# SMC_FrontPanel_ExtensionBoard_V14_5.net
KiCad netlist of a schematic drawn in EAGLE
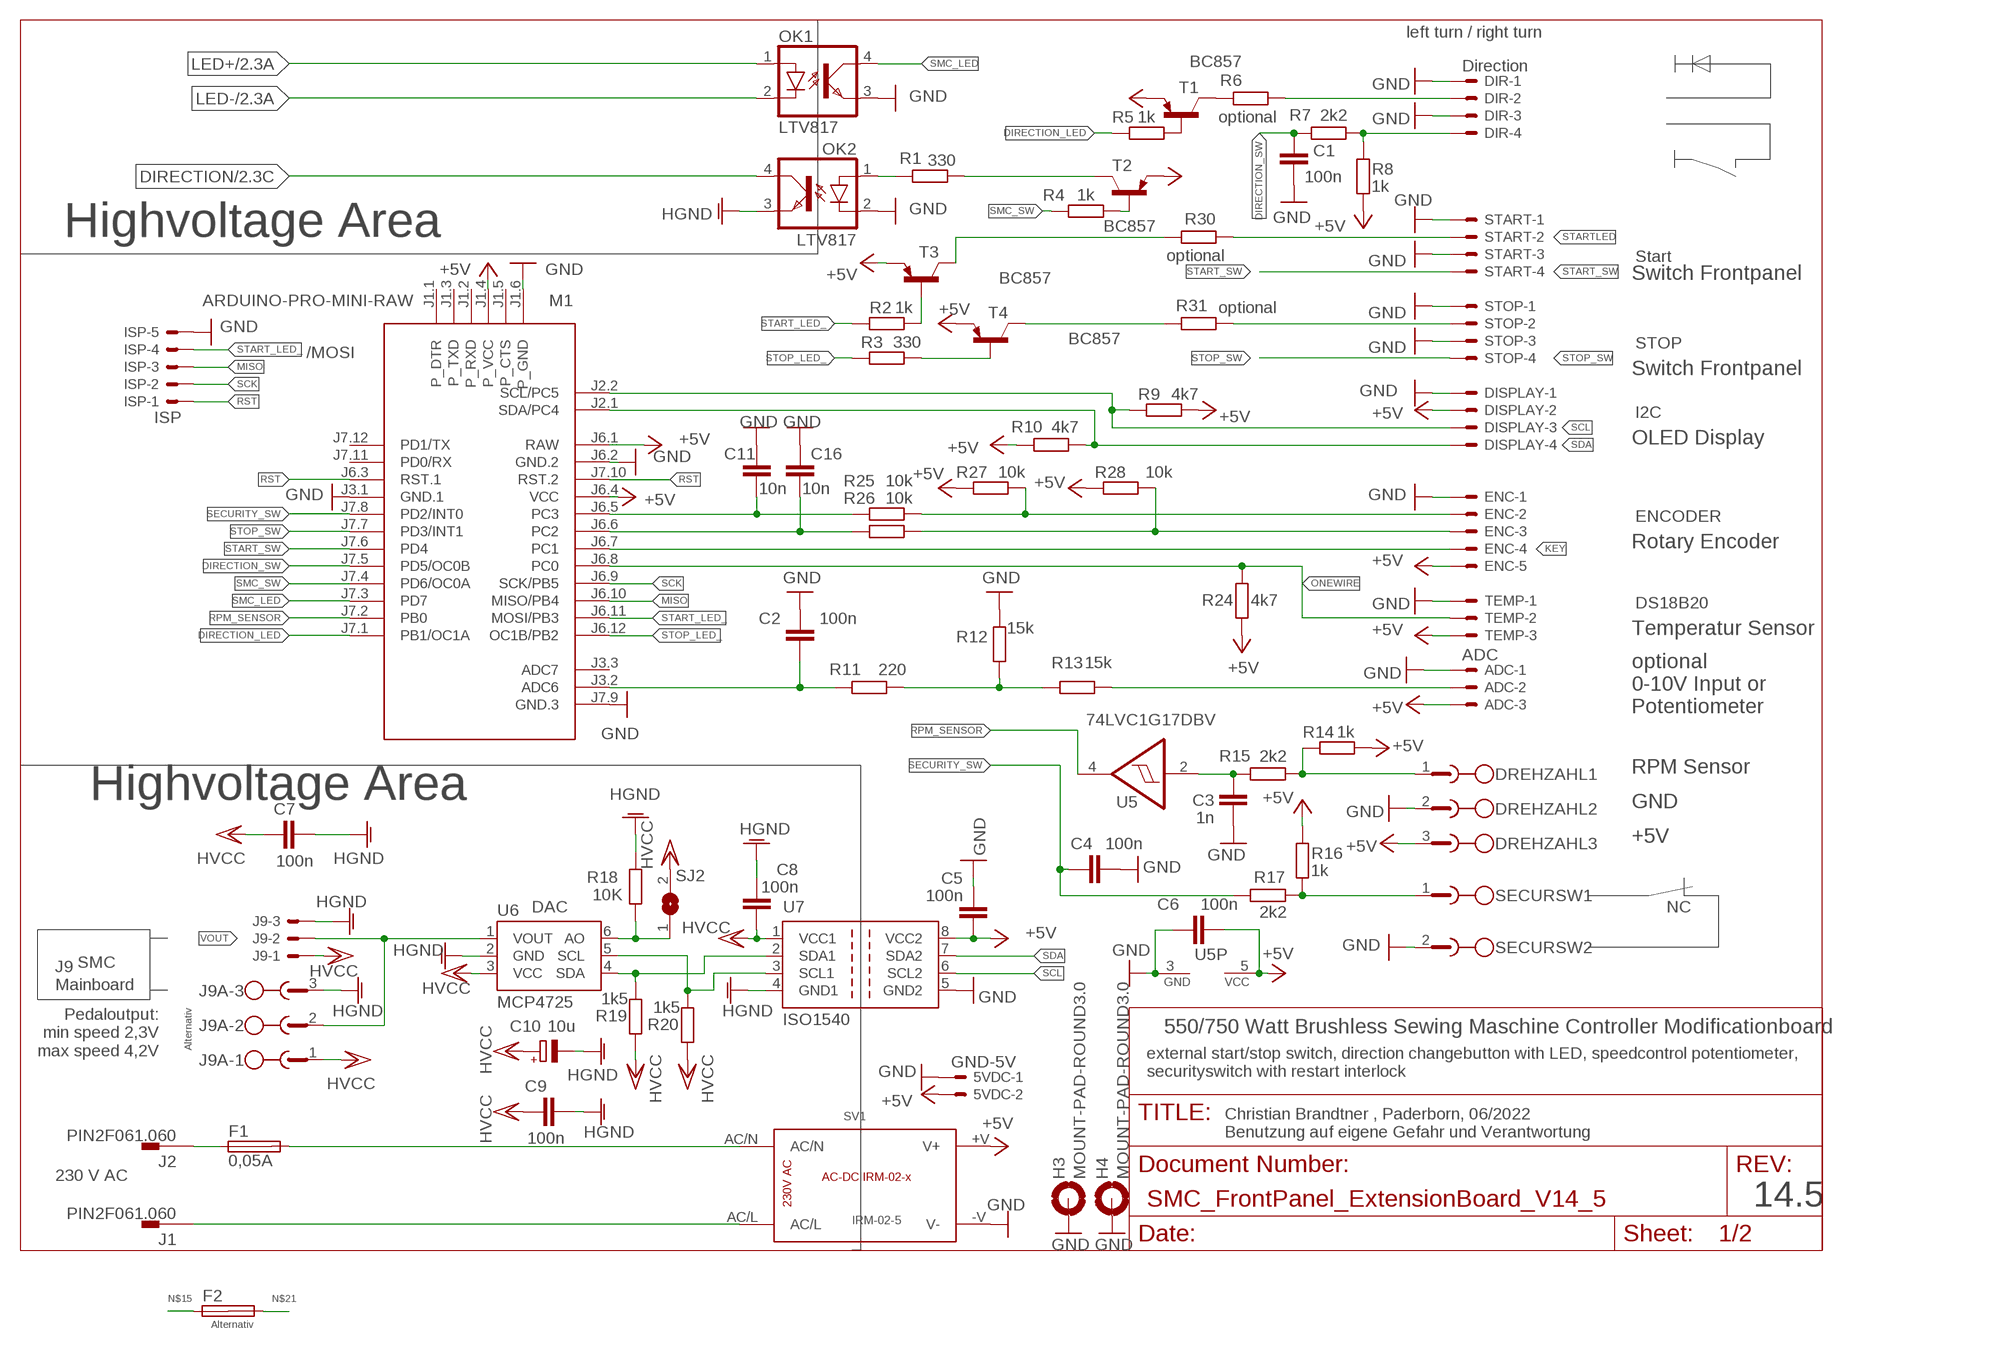
[diagram p0: schematic, sheet 1]
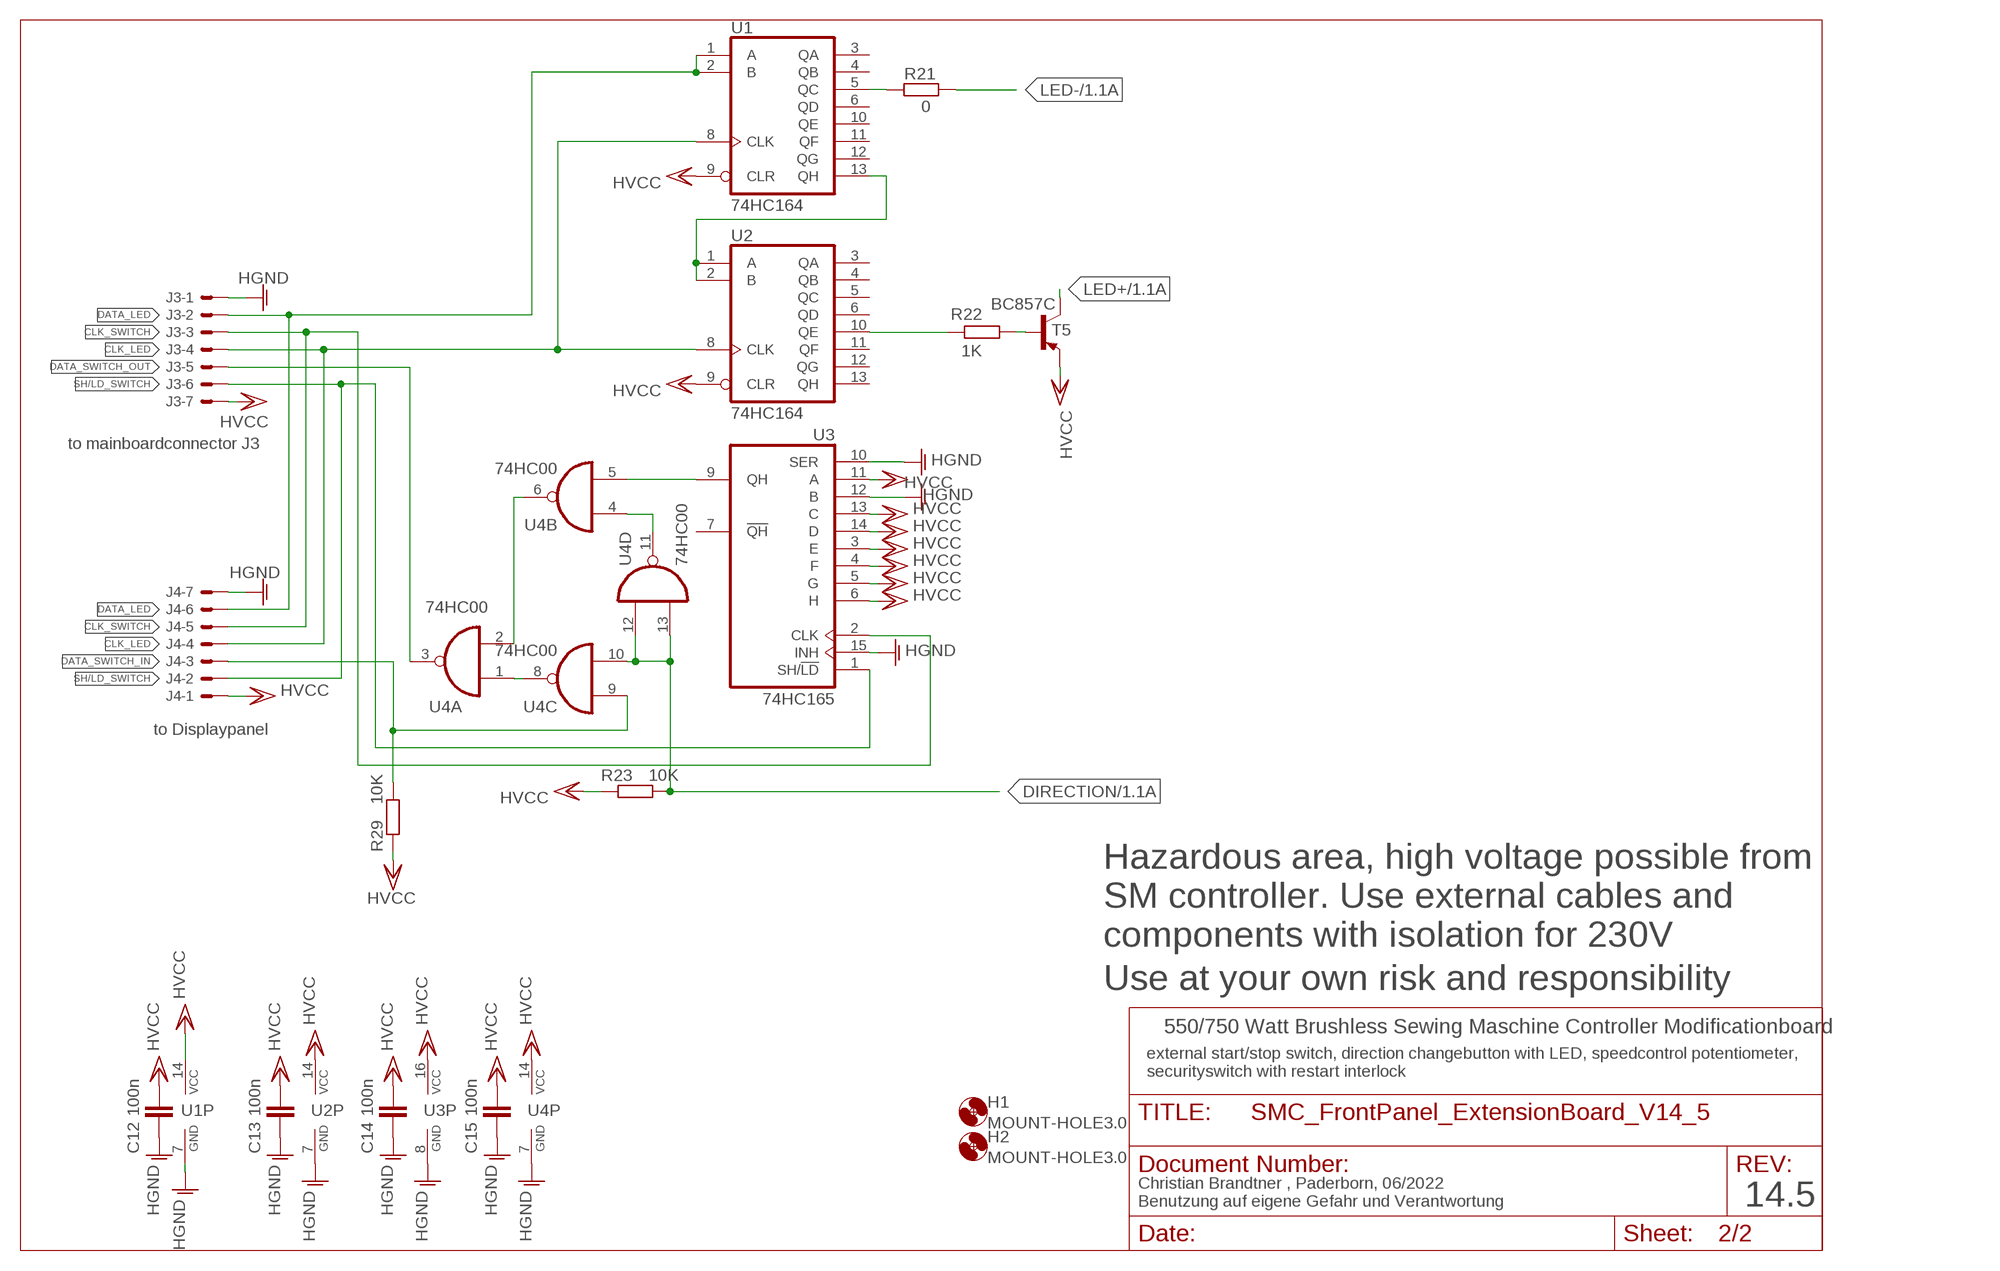
[diagram p1: schematic, sheet 2]

(export (version "E")
  (design (tool "Eeschema 10.0.6"))
  (components
    (comp (ref "C12")
      (value "100n")
      (footprint "eagle-import:C0805")
      (libsource (lib "eagle-import") (part "C-EUC0805"))
    )
    (comp (ref "C13")
      (value "100n")
      (footprint "eagle-import:C0805")
      (libsource (lib "eagle-import") (part "C-EUC0805"))
    )
    (comp (ref "C14")
      (value "100n")
      (footprint "eagle-import:C0805")
      (libsource (lib "eagle-import") (part "C-EUC0805"))
    )
    (comp (ref "C15")
      (value "100n")
      (footprint "eagle-import:C0805")
      (libsource (lib "eagle-import") (part "C-EUC0805"))
    )
    (comp (ref "H1")
      (value "MOUNT-HOLE3.0")
      (footprint "eagle-import:3,0")
      (libsource (lib "eagle-import") (part "MOUNT-HOLE3.0"))
    )
    (comp (ref "H2")
      (value "MOUNT-HOLE3.0")
      (footprint "eagle-import:3,0")
      (libsource (lib "eagle-import") (part "MOUNT-HOLE3.0"))
    )
    (comp (ref "J3")
      (value "to mainboardconnector J3")
      (footprint "eagle-import:JST-XH-07-PACKAGE-ROUND-PAD")
      (libsource (lib "eagle-import") (part "JST-XH-07-PIN-ROUND-PAD"))
    )
    (comp (ref "J4")
      (value "to Displaypanel")
      (footprint "eagle-import:JST-XH-07-PACKAGE-ROUND-PAD")
      (libsource (lib "eagle-import") (part "JST-XH-07-PIN-ROUND-PAD"))
    )
    (comp (ref "R21")
      (value "0")
      (footprint "eagle-import:R0805")
      (libsource (lib "eagle-import") (part "R-EU_R0805"))
    )
    (comp (ref "R22")
      (value "1K")
      (footprint "eagle-import:R0805")
      (libsource (lib "eagle-import") (part "R-EU_R0805"))
    )
    (comp (ref "R23")
      (value "10K")
      (footprint "eagle-import:R0805")
      (libsource (lib "eagle-import") (part "R-EU_R0805"))
    )
    (comp (ref "R29")
      (value "10K")
      (footprint "eagle-import:R0805")
      (libsource (lib "eagle-import") (part "R-EU_R0805"))
    )
    (comp (ref "T5")
      (value "BC857C")
      (footprint "eagle-import:SOT23-BEC")
      (libsource (lib "eagle-import") (part "-PNP-SOT23-BECBC857C"))
    )
    (comp (ref "U1")
      (value "74HC164")
      (footprint "eagle-import:SO14")
      (libsource (lib "eagle-import") (part "74164DHC"))
    )
    (comp (ref "U2")
      (value "74HC164")
      (footprint "eagle-import:SO14")
      (libsource (lib "eagle-import") (part "74164DHC"))
    )
    (comp (ref "U3")
      (value "74HC165")
      (footprint "eagle-import:SO16")
      (libsource (lib "eagle-import") (part "74165DHC"))
    )
    (comp (ref "U4")
      (value "74HC00")
      (footprint "eagle-import:SO14")
      (libsource (lib "eagle-import") (part "7400DHC"))
    )
    (comp (ref "5VDC")
      (value "GND-5V")
      (footprint "eagle-import:JST-XH-02-PACKAGE-ROUND-PAD")
      (libsource (lib "eagle-import") (part "JST-XH-02-PIN-ROUND-PAD"))
    )
    (comp (ref "ADC")
      (value "ADC")
      (footprint "eagle-import:JST-XH-03-PACKAGE-ROUND-PAD")
      (libsource (lib "eagle-import") (part "JST-XH-03-PIN-ROUND-PAD"))
    )
    (comp (ref "C1")
      (value "100n")
      (footprint "eagle-import:C0805")
      (libsource (lib "eagle-import") (part "C-EUC0805"))
    )
    (comp (ref "C2")
      (value "100n")
      (footprint "eagle-import:C0805")
      (libsource (lib "eagle-import") (part "C-EUC0805"))
    )
    (comp (ref "C3")
      (value "1n")
      (footprint "eagle-import:C0805")
      (libsource (lib "eagle-import") (part "C-EUC0805"))
    )
    (comp (ref "C4")
      (value "100n")
      (footprint "eagle-import:C0805")
      (libsource (lib "eagle-import") (part "C-EUC0805"))
    )
    (comp (ref "C5")
      (value "100n")
      (footprint "eagle-import:C0805")
      (libsource (lib "eagle-import") (part "C-EUC0805"))
    )
    (comp (ref "C6")
      (value "100n")
      (footprint "eagle-import:C0805")
      (libsource (lib "eagle-import") (part "C-EUC0805"))
    )
    (comp (ref "C7")
      (value "100n")
      (footprint "eagle-import:C0805")
      (libsource (lib "eagle-import") (part "C-EUC0805"))
    )
    (comp (ref "C8")
      (value "100n")
      (footprint "eagle-import:C0805")
      (libsource (lib "eagle-import") (part "C-EUC0805"))
    )
    (comp (ref "C9")
      (value "100n")
      (footprint "eagle-import:C0805")
      (libsource (lib "eagle-import") (part "C-EUC0805"))
    )
    (comp (ref "C10")
      (value "10u")
      (footprint "eagle-import:153CLV-0405")
      (libsource (lib "eagle-import") (part "CPOL-EU153CLV-0405"))
    )
    (comp (ref "C11")
      (value "10n")
      (footprint "eagle-import:C0805")
      (libsource (lib "eagle-import") (part "C-EUC0805"))
    )
    (comp (ref "C16")
      (value "10n")
      (footprint "eagle-import:C0805")
      (libsource (lib "eagle-import") (part "C-EUC0805"))
    )
    (comp (ref "DIR")
      (value "Direction")
      (footprint "eagle-import:JST-XH-04-PACKAGE-ROUND-PAD")
      (libsource (lib "eagle-import") (part "JST-XH-04-PIN-ROUND-PAD"))
    )
    (comp (ref "DISPLAY")
      (value "I2C")
      (footprint "eagle-import:JST-XH-04-PACKAGE-ROUND-PAD")
      (libsource (lib "eagle-import") (part "JST-XH-04-PIN-ROUND-PAD"))
    )
    (comp (ref "DREHZAHL")
      (value "MCV_1.5/3/-G-3.5")
      (footprint "eagle-import:1843619")
      (libsource (lib "eagle-import") (part "MCV_1.5/3/-G-3.5"))
    )
    (comp (ref "ENC")
      (value "ENCODER")
      (footprint "eagle-import:JST-XH-05-PACKAGE-ROUND-PAD")
      (libsource (lib "eagle-import") (part "JST-XH-05-PIN-ROUND-PAD"))
    )
    (comp (ref "F1")
      (value "0,05A")
      (footprint "eagle-import:MTA501100")
      (libsource (lib "eagle-import") (part "FUSE"))
    )
    (comp (ref "F2")
      (value "SHK20L")
      (footprint "eagle-import:SHK20L")
      (libsource (lib "eagle-import") (part "SHK20L"))
    )
    (comp (ref "H3")
      (value "MOUNT-PAD-ROUND3.0")
      (footprint "eagle-import:3,0-PAD")
      (libsource (lib "eagle-import") (part "MOUNT-PAD-ROUND3.0"))
    )
    (comp (ref "H4")
      (value "MOUNT-PAD-ROUND3.0")
      (footprint "eagle-import:3,0-PAD")
      (libsource (lib "eagle-import") (part "MOUNT-PAD-ROUND3.0"))
    )
    (comp (ref "ISP")
      (value "ISP")
      (footprint "eagle-import:JST-XH-05-PACKAGE-ROUND-PAD")
      (libsource (lib "eagle-import") (part "JST-XH-05-PIN-ROUND-PAD"))
    )
    (comp (ref "J1")
      (value "PIN2F061.060")
      (footprint "eagle-import:F061.060")
      (libsource (lib "eagle-import") (part "PIN2F061.060"))
    )
    (comp (ref "J2")
      (value "PIN2F061.060")
      (footprint "eagle-import:F061.060")
      (libsource (lib "eagle-import") (part "PIN2F061.060"))
    )
    (comp (ref "J9")
      (value "JST-XH-03-PIN-ROUND-PAD")
      (footprint "eagle-import:JST-XH-03-PACKAGE-ROUND-PAD")
      (libsource (lib "eagle-import") (part "JST-XH-03-PIN-ROUND-PAD"))
    )
    (comp (ref "J9A-")
      (value "MCV_1.5/3/-G-3.5")
      (footprint "eagle-import:1843619")
      (libsource (lib "eagle-import") (part "MCV_1.5/3/-G-3.5"))
    )
    (comp (ref "M1")
      (value "ARDUINO-PRO-MINI-RAW")
      (footprint "eagle-import:ARDUINO-PRO-MINI")
      (libsource (lib "eagle-import") (part "ARDUINO-PRO-MINI-RAW"))
    )
    (comp (ref "OK1")
      (value "LTV817")
      (footprint "eagle-import:SMD4-7")
      (fields (field (name "MF") "VISHAY/TELEFUNKEN") (field (name "MPN") "SFH6186-2"))
      (libsource (lib "eagle-import") (part "SFH618?6-2"))
    )
    (comp (ref "OK2")
      (value "LTV817")
      (footprint "eagle-import:SMD4-7")
      (fields (field (name "MF") "VISHAY/TELEFUNKEN") (field (name "MPN") "SFH6186-2"))
      (libsource (lib "eagle-import") (part "SFH618?6-2"))
    )
    (comp (ref "R1")
      (value "330")
      (footprint "eagle-import:R0805")
      (libsource (lib "eagle-import") (part "R-EU_R0805"))
    )
    (comp (ref "R2")
      (value "1k")
      (footprint "eagle-import:R0805")
      (libsource (lib "eagle-import") (part "R-EU_R0805"))
    )
    (comp (ref "R3")
      (value "330")
      (footprint "eagle-import:R0805")
      (libsource (lib "eagle-import") (part "R-EU_R0805"))
    )
    (comp (ref "R4")
      (value "1k")
      (footprint "eagle-import:R0805")
      (libsource (lib "eagle-import") (part "R-EU_R0805"))
    )
    (comp (ref "R5")
      (value "1k")
      (footprint "eagle-import:R0805")
      (libsource (lib "eagle-import") (part "R-EU_R0805"))
    )
    (comp (ref "R6")
      (value "optional")
      (footprint "eagle-import:R0805")
      (libsource (lib "eagle-import") (part "R-EU_R0805"))
    )
    (comp (ref "R7")
      (value "2k2")
      (footprint "eagle-import:R0805")
      (libsource (lib "eagle-import") (part "R-EU_R0805"))
    )
    (comp (ref "R8")
      (value "1k")
      (footprint "eagle-import:R0805")
      (libsource (lib "eagle-import") (part "R-EU_R0805"))
    )
    (comp (ref "R9")
      (value "4k7")
      (footprint "eagle-import:R0805")
      (libsource (lib "eagle-import") (part "R-EU_R0805"))
    )
    (comp (ref "R10")
      (value "4k7")
      (footprint "eagle-import:R0805")
      (libsource (lib "eagle-import") (part "R-EU_R0805"))
    )
    (comp (ref "R11")
      (value "220")
      (footprint "eagle-import:R0805")
      (libsource (lib "eagle-import") (part "R-EU_R0805"))
    )
    (comp (ref "R12")
      (value "15k")
      (footprint "eagle-import:R0805")
      (libsource (lib "eagle-import") (part "R-EU_R0805"))
    )
    (comp (ref "R13")
      (value "15k")
      (footprint "eagle-import:R0805")
      (libsource (lib "eagle-import") (part "R-EU_R0805"))
    )
    (comp (ref "R14")
      (value "1k")
      (footprint "eagle-import:R0805")
      (libsource (lib "eagle-import") (part "R-EU_R0805"))
    )
    (comp (ref "R15")
      (value "2k2")
      (footprint "eagle-import:R0805")
      (libsource (lib "eagle-import") (part "R-EU_R0805"))
    )
    (comp (ref "R16")
      (value "1k")
      (footprint "eagle-import:R0805")
      (libsource (lib "eagle-import") (part "R-EU_R0805"))
    )
    (comp (ref "R17")
      (value "2k2")
      (footprint "eagle-import:R0805")
      (libsource (lib "eagle-import") (part "R-EU_R0805"))
    )
    (comp (ref "R18")
      (value "10K")
      (footprint "eagle-import:R0805")
      (libsource (lib "eagle-import") (part "R-EU_R0805"))
    )
    (comp (ref "R19")
      (value "1k5")
      (footprint "eagle-import:R0805")
      (libsource (lib "eagle-import") (part "R-EU_R0805"))
    )
    (comp (ref "R20")
      (value "1k5")
      (footprint "eagle-import:R0805")
      (libsource (lib "eagle-import") (part "R-EU_R0805"))
    )
    (comp (ref "R24")
      (value "4k7")
      (footprint "eagle-import:R0805")
      (libsource (lib "eagle-import") (part "R-EU_R0805"))
    )
    (comp (ref "R25")
      (value "10k")
      (footprint "eagle-import:R0805")
      (libsource (lib "eagle-import") (part "R-EU_R0805"))
    )
    (comp (ref "R26")
      (value "10k")
      (footprint "eagle-import:R0805")
      (libsource (lib "eagle-import") (part "R-EU_R0805"))
    )
    (comp (ref "R27")
      (value "10k")
      (footprint "eagle-import:R0805")
      (libsource (lib "eagle-import") (part "R-EU_R0805"))
    )
    (comp (ref "R28")
      (value "10k")
      (footprint "eagle-import:R0805")
      (libsource (lib "eagle-import") (part "R-EU_R0805"))
    )
    (comp (ref "R30")
      (value "optional")
      (footprint "eagle-import:R0805")
      (libsource (lib "eagle-import") (part "R-EU_R0805"))
    )
    (comp (ref "R31")
      (value "optional")
      (footprint "eagle-import:R0805")
      (libsource (lib "eagle-import") (part "R-EU_R0805"))
    )
    (comp (ref "SECURSW")
      (value "MCV_1,5/2-G-3,5")
      (footprint "eagle-import:1843606")
      (libsource (lib "eagle-import") (part "MCV_1,5/2-G-3,5"))
    )
    (comp (ref "SJ2") (value "SJ") (footprint "eagle-import:SJ") (libsource (lib "eagle-import") (part "SJ")))
    (comp (ref "START")
      (value "Start")
      (footprint "eagle-import:JST-XH-04-PACKAGE-ROUND-PAD")
      (libsource (lib "eagle-import") (part "JST-XH-04-PIN-ROUND-PAD"))
    )
    (comp (ref "STOP")
      (value "STOP")
      (footprint "eagle-import:JST-XH-04-PACKAGE-ROUND-PAD")
      (libsource (lib "eagle-import") (part "JST-XH-04-PIN-ROUND-PAD"))
    )
    (comp (ref "SV1")
      (value "IRM-02-5")
      (footprint "eagle-import:IRM-02-X")
      (libsource (lib "eagle-import") (part "IRM-02-X"))
    )
    (comp (ref "T1")
      (value "BC857")
      (footprint "eagle-import:SOT23-BEC")
      (libsource (lib "eagle-import") (part "BC857SMDA"))
    )
    (comp (ref "T2")
      (value "BC857")
      (footprint "eagle-import:SOT23-BEC")
      (libsource (lib "eagle-import") (part "BC857SMDA"))
    )
    (comp (ref "T3")
      (value "BC857")
      (footprint "eagle-import:SOT23-BEC")
      (libsource (lib "eagle-import") (part "BC857SMDA"))
    )
    (comp (ref "T4")
      (value "BC857")
      (footprint "eagle-import:SOT23-BEC")
      (libsource (lib "eagle-import") (part "BC857SMDA"))
    )
    (comp (ref "TEMP")
      (value "DS18B20")
      (footprint "eagle-import:JST-XH-03-PACKAGE-ROUND-PAD")
      (libsource (lib "eagle-import") (part "JST-XH-03-PIN-ROUND-PAD"))
    )
    (comp (ref "U5")
      (value "74LVC1G17DBV")
      (footprint "eagle-import:SOT23-5")
      (libsource (lib "eagle-import") (part "741G17DBVLVC"))
    )
    (comp (ref "U6")
      (value "MCP4725")
      (footprint "eagle-import:SOT23-6")
      (libsource (lib "eagle-import") (part "MCP4725SOT-23"))
    )
    (comp (ref "U7")
      (value "ISO1540")
      (footprint "eagle-import:SO-08")
      (libsource (lib "eagle-import") (part "ISO1540"))
    )
  )
  (nets
    (net (code "1") (name "+5V") (class "Default")
      (node (ref "5VDC") (pin "2") (pinfunction "S_2") (pintype "passive"))
      (node (ref "ADC") (pin "3") (pinfunction "S_3") (pintype "passive"))
      (node (ref "C5") (pin "1") (pinfunction "1_1") (pintype "passive"))
      (node (ref "C6") (pin "1") (pinfunction "1_1") (pintype "passive"))
      (node (ref "DISPLAY") (pin "2") (pinfunction "S_2") (pintype "passive"))
      (node (ref "DREHZAHL") (pin "3") (pinfunction "1_3") (pintype "passive"))
      (node (ref "ENC") (pin "5") (pinfunction "S_5") (pintype "passive"))
      (node (ref "M1") (pin "J1.4") (pinfunction "P_VCC_J1.4") (pintype "bidirectional"))
      (node (ref "M1") (pin "J6.1") (pinfunction "RAW_J6.1") (pintype "power_in"))
      (node (ref "M1") (pin "J6.4") (pinfunction "VCC_J6.4") (pintype "power_in"))
      (node (ref "R10") (pin "1") (pinfunction "1_1") (pintype "passive"))
      (node (ref "R14") (pin "1") (pinfunction "1_1") (pintype "passive"))
      (node (ref "R16") (pin "1") (pinfunction "1_1") (pintype "passive"))
      (node (ref "R24") (pin "2") (pinfunction "2_2") (pintype "passive"))
      (node (ref "R27") (pin "1") (pinfunction "1_1") (pintype "passive"))
      (node (ref "R28") (pin "1") (pinfunction "1_1") (pintype "passive"))
      (node (ref "R8") (pin "2") (pinfunction "2_2") (pintype "passive"))
      (node (ref "R9") (pin "1") (pinfunction "1_1") (pintype "passive"))
      (node (ref "SV1") (pin "+V") (pinfunction "V+_+V") (pintype "bidirectional"))
      (node (ref "T1") (pin "E") (pinfunction "E_E") (pintype "passive"))
      (node (ref "T2") (pin "E") (pinfunction "E_E") (pintype "passive"))
      (node (ref "T3") (pin "E") (pinfunction "E_E") (pintype "passive"))
      (node (ref "T4") (pin "E") (pinfunction "E_E") (pintype "passive"))
      (node (ref "TEMP") (pin "3") (pinfunction "S_3") (pintype "passive"))
      (node (ref "U5") (pin "5") (pinfunction "VCC_5") (pintype "power_in"))
      (node (ref "U7") (pin "8") (pinfunction "VCC2_8") (pintype "power_in"))
    )
    (net (code "2") (name "CLK_LED") (class "Default")
      (node (ref "J3") (pin "4") (pinfunction "S_4") (pintype "passive"))
      (node (ref "J4") (pin "4") (pinfunction "S_4") (pintype "passive"))
      (node (ref "U1") (pin "8") (pinfunction "CLK_8") (pintype "input"))
      (node (ref "U2") (pin "8") (pinfunction "CLK_8") (pintype "input"))
    )
    (net (code "3") (name "CLK_SWITCH") (class "Default")
      (node (ref "J3") (pin "3") (pinfunction "S_3") (pintype "passive"))
      (node (ref "J4") (pin "5") (pinfunction "S_5") (pintype "passive"))
      (node (ref "U3") (pin "2") (pinfunction "CLK_2") (pintype "input"))
    )
    (net (code "4") (name "DATA_LED") (class "Default")
      (node (ref "J3") (pin "2") (pinfunction "S_2") (pintype "passive"))
      (node (ref "J4") (pin "6") (pinfunction "S_6") (pintype "passive"))
      (node (ref "U1") (pin "1") (pinfunction "A_1") (pintype "input"))
      (node (ref "U1") (pin "2") (pinfunction "B_2") (pintype "input"))
    )
    (net (code "5") (name "DATA_SWITCH_IN") (class "Default")
      (node (ref "J4") (pin "3") (pinfunction "S_3") (pintype "passive"))
      (node (ref "R29") (pin "1") (pinfunction "1_1") (pintype "passive"))
      (node (ref "U4") (pin "9") (pinfunction "I0_9") (pintype "input"))
    )
    (net (code "6") (name "DATA_SWITCH_OUT") (class "Default")
      (node (ref "J3") (pin "5") (pinfunction "S_5") (pintype "passive"))
      (node (ref "U4") (pin "3") (pinfunction "O_3") (pintype "output"))
    )
    (net (code "7") (name "DIRECTION") (class "Default")
      (node (ref "OK2") (pin "4") (pinfunction "COL_4") (pintype "passive"))
      (node (ref "R23") (pin "1") (pinfunction "1_1") (pintype "passive"))
      (node (ref "U4") (pin "10") (pinfunction "I1_10") (pintype "input"))
      (node (ref "U4") (pin "12") (pinfunction "I0_12") (pintype "input"))
      (node (ref "U4") (pin "13") (pinfunction "I1_13") (pintype "input"))
    )
    (net (code "8") (name "DIRECTION_LED") (class "Default")
      (node (ref "M1") (pin "J7.1") (pinfunction "PB1/OC1A_J7.1") (pintype "bidirectional"))
      (node (ref "R5") (pin "2") (pinfunction "2_2") (pintype "passive"))
    )
    (net (code "9") (name "DIRECTION_SW") (class "Default")
      (node (ref "C1") (pin "2") (pinfunction "2_2") (pintype "passive"))
      (node (ref "M1") (pin "J7.5") (pinfunction "PD5/OC0B_J7.5") (pintype "bidirectional"))
      (node (ref "R7") (pin "1") (pinfunction "1_1") (pintype "passive"))
    )
    (net (code "10") (name "GND") (class "Default")
      (node (ref "5VDC") (pin "1") (pinfunction "S_1") (pintype "passive"))
      (node (ref "ADC") (pin "1") (pinfunction "S_1") (pintype "passive"))
      (node (ref "C1") (pin "1") (pinfunction "1_1") (pintype "passive"))
      (node (ref "C11") (pin "2") (pinfunction "2_2") (pintype "passive"))
      (node (ref "C16") (pin "2") (pinfunction "2_2") (pintype "passive"))
      (node (ref "C2") (pin "2") (pinfunction "2_2") (pintype "passive"))
      (node (ref "C3") (pin "1") (pinfunction "1_1") (pintype "passive"))
      (node (ref "C4") (pin "2") (pinfunction "2_2") (pintype "passive"))
      (node (ref "C5") (pin "2") (pinfunction "2_2") (pintype "passive"))
      (node (ref "C6") (pin "2") (pinfunction "2_2") (pintype "passive"))
      (node (ref "DIR") (pin "1") (pinfunction "S_1") (pintype "passive"))
      (node (ref "DIR") (pin "3") (pinfunction "S_3") (pintype "passive"))
      (node (ref "DISPLAY") (pin "1") (pinfunction "S_1") (pintype "passive"))
      (node (ref "DREHZAHL") (pin "2") (pinfunction "1_2") (pintype "passive"))
      (node (ref "ENC") (pin "1") (pinfunction "S_1") (pintype "passive"))
      (node (ref "H3") (pin "B3,0") (pinfunction "MOUNT_B3,0") (pintype "passive"))
      (node (ref "H4") (pin "B3,0") (pinfunction "MOUNT_B3,0") (pintype "passive"))
      (node (ref "ISP") (pin "5") (pinfunction "S_5") (pintype "passive"))
      (node (ref "M1") (pin "J1.6") (pinfunction "P_GND_J1.6") (pintype "bidirectional"))
      (node (ref "M1") (pin "J3.1") (pinfunction "GND.1_J3.1") (pintype "power_in"))
      (node (ref "M1") (pin "J6.2") (pinfunction "GND.2_J6.2") (pintype "power_in"))
      (node (ref "M1") (pin "J7.9") (pinfunction "GND.3_J7.9") (pintype "bidirectional"))
      (node (ref "OK1") (pin "3") (pinfunction "EMIT_3") (pintype "passive"))
      (node (ref "OK2") (pin "2") (pinfunction "C_2") (pintype "passive"))
      (node (ref "R12") (pin "2") (pinfunction "2_2") (pintype "passive"))
      (node (ref "SECURSW") (pin "2") (pinfunction "1_2") (pintype "passive"))
      (node (ref "START") (pin "1") (pinfunction "S_1") (pintype "passive"))
      (node (ref "START") (pin "3") (pinfunction "S_3") (pintype "passive"))
      (node (ref "STOP") (pin "1") (pinfunction "S_1") (pintype "passive"))
      (node (ref "STOP") (pin "3") (pinfunction "S_3") (pintype "passive"))
      (node (ref "SV1") (pin "-V") (pinfunction "V-_-V") (pintype "bidirectional"))
      (node (ref "TEMP") (pin "1") (pinfunction "S_1") (pintype "passive"))
      (node (ref "U5") (pin "3") (pinfunction "GND_3") (pintype "power_in"))
      (node (ref "U7") (pin "5") (pinfunction "GND2_5") (pintype "power_in"))
    )
    (net (code "11") (name "HGND") (class "Default")
      (node (ref "C10") (pin "-") (pinfunction "-_-") (pintype "passive"))
      (node (ref "C12") (pin "1") (pinfunction "1_1") (pintype "passive"))
      (node (ref "C13") (pin "1") (pinfunction "1_1") (pintype "passive"))
      (node (ref "C14") (pin "1") (pinfunction "1_1") (pintype "passive"))
      (node (ref "C15") (pin "1") (pinfunction "1_1") (pintype "passive"))
      (node (ref "C7") (pin "1") (pinfunction "1_1") (pintype "passive"))
      (node (ref "C8") (pin "2") (pinfunction "2_2") (pintype "passive"))
      (node (ref "C9") (pin "1") (pinfunction "1_1") (pintype "passive"))
      (node (ref "J3") (pin "1") (pinfunction "S_1") (pintype "passive"))
      (node (ref "J4") (pin "7") (pinfunction "S_7") (pintype "passive"))
      (node (ref "J9") (pin "3") (pinfunction "S_3") (pintype "passive"))
      (node (ref "J9A-") (pin "3") (pinfunction "1_3") (pintype "passive"))
      (node (ref "OK2") (pin "3") (pinfunction "EMIT_3") (pintype "passive"))
      (node (ref "R18") (pin "1") (pinfunction "1_1") (pintype "passive"))
      (node (ref "U1") (pin "7") (pinfunction "GND_7") (pintype "power_in"))
      (node (ref "U2") (pin "7") (pinfunction "GND_7") (pintype "power_in"))
      (node (ref "U3") (pin "10") (pinfunction "SER_10") (pintype "input"))
      (node (ref "U3") (pin "12") (pinfunction "B_12") (pintype "input"))
      (node (ref "U3") (pin "15") (pinfunction "INH_15") (pintype "input"))
      (node (ref "U3") (pin "8") (pinfunction "GND_8") (pintype "power_in"))
      (node (ref "U4") (pin "7") (pinfunction "GND_7") (pintype "power_in"))
      (node (ref "U6") (pin "2") (pinfunction "GND_2") (pintype "bidirectional"))
      (node (ref "U7") (pin "4") (pinfunction "GND1_4") (pintype "power_in"))
    )
    (net (code "12") (name "HVCC") (class "Default")
      (node (ref "C10") (pin "+") (pinfunction "+_+") (pintype "passive"))
      (node (ref "C12") (pin "2") (pinfunction "2_2") (pintype "passive"))
      (node (ref "C13") (pin "2") (pinfunction "2_2") (pintype "passive"))
      (node (ref "C14") (pin "2") (pinfunction "2_2") (pintype "passive"))
      (node (ref "C15") (pin "2") (pinfunction "2_2") (pintype "passive"))
      (node (ref "C7") (pin "2") (pinfunction "2_2") (pintype "passive"))
      (node (ref "C8") (pin "1") (pinfunction "1_1") (pintype "passive"))
      (node (ref "C9") (pin "2") (pinfunction "2_2") (pintype "passive"))
      (node (ref "J3") (pin "7") (pinfunction "S_7") (pintype "passive"))
      (node (ref "J4") (pin "1") (pinfunction "S_1") (pintype "passive"))
      (node (ref "J9") (pin "1") (pinfunction "S_1") (pintype "passive"))
      (node (ref "J9A-") (pin "1") (pinfunction "1_1") (pintype "passive"))
      (node (ref "R19") (pin "2") (pinfunction "2_2") (pintype "passive"))
      (node (ref "R20") (pin "2") (pinfunction "2_2") (pintype "passive"))
      (node (ref "R23") (pin "2") (pinfunction "2_2") (pintype "passive"))
      (node (ref "R29") (pin "2") (pinfunction "2_2") (pintype "passive"))
      (node (ref "SJ2") (pin "2") (pinfunction "2_2") (pintype "passive"))
      (node (ref "T5") (pin "E") (pinfunction "E_E") (pintype "passive"))
      (node (ref "U1") (pin "14") (pinfunction "VCC_14") (pintype "power_in"))
      (node (ref "U1") (pin "9") (pinfunction "CLR_9") (pintype "input"))
      (node (ref "U2") (pin "14") (pinfunction "VCC_14") (pintype "power_in"))
      (node (ref "U2") (pin "9") (pinfunction "CLR_9") (pintype "input"))
      (node (ref "U3") (pin "11") (pinfunction "A_11") (pintype "input"))
      (node (ref "U3") (pin "13") (pinfunction "C_13") (pintype "input"))
      (node (ref "U3") (pin "14") (pinfunction "D_14") (pintype "input"))
      (node (ref "U3") (pin "16") (pinfunction "VCC_16") (pintype "power_in"))
      (node (ref "U3") (pin "3") (pinfunction "E_3") (pintype "input"))
      (node (ref "U3") (pin "4") (pinfunction "F_4") (pintype "input"))
      (node (ref "U3") (pin "5") (pinfunction "G_5") (pintype "input"))
      (node (ref "U3") (pin "6") (pinfunction "H_6") (pintype "input"))
      (node (ref "U4") (pin "14") (pinfunction "VCC_14") (pintype "power_in"))
      (node (ref "U6") (pin "3") (pinfunction "VCC_3") (pintype "bidirectional"))
      (node (ref "U7") (pin "1") (pinfunction "VCC1_1") (pintype "power_in"))
    )
    (net (code "13") (name "KEY") (class "Default")
      (node (ref "ENC") (pin "4") (pinfunction "S_4") (pintype "passive"))
      (node (ref "M1") (pin "J6.7") (pinfunction "PC1_J6.7") (pintype "bidirectional"))
    )
    (net (code "14") (name "LED+") (class "Default")
      (node (ref "OK1") (pin "1") (pinfunction "A_1") (pintype "passive"))
      (node (ref "T5") (pin "C") (pinfunction "C_C") (pintype "passive"))
    )
    (net (code "15") (name "LED-") (class "Default")
      (node (ref "OK1") (pin "2") (pinfunction "C_2") (pintype "passive"))
      (node (ref "R21") (pin "2") (pinfunction "2_2") (pintype "passive"))
    )
    (net (code "16") (name "MISO") (class "Default")
      (node (ref "ISP") (pin "3") (pinfunction "S_3") (pintype "passive"))
      (node (ref "M1") (pin "J6.10") (pinfunction "MISO/PB4_J6.10") (pintype "bidirectional"))
    )
    (net (code "17") (name "N$15") (class "Default")
      (node (ref "F1") (pin "1") (pinfunction "1_1") (pintype "passive"))
      (node (ref "F2") (pin "1A") (pinfunction "1A_1A") (pintype "passive"))
      (node (ref "J2") (pin "A1") (pinfunction "1_A1") (pintype "passive"))
      (node (ref "J2") (pin "A2") (pinfunction "1_A2") (pintype "passive"))
    )
    (net (code "18") (name "N$21") (class "Default")
      (node (ref "F1") (pin "2") (pinfunction "2_2") (pintype "passive"))
      (node (ref "F2") (pin "2A") (pinfunction "2A_2A") (pintype "passive"))
      (node (ref "SV1") (pin "AC/N") (pinfunction "AC/N_AC/N") (pintype "bidirectional"))
    )
    (net (code "19") (name "Net-(ADCB-S)") (class "Default")
      (node (ref "ADC") (pin "2") (pinfunction "S_2") (pintype "passive"))
      (node (ref "R13") (pin "1") (pinfunction "1_1") (pintype "passive"))
    )
    (net (code "20") (name "Net-(DIRB-S)") (class "Default")
      (node (ref "DIR") (pin "2") (pinfunction "S_2") (pintype "passive"))
      (node (ref "R6") (pin "1") (pinfunction "1_1") (pintype "passive"))
    )
    (net (code "21") (name "Net-(DIRD-S)") (class "Default")
      (node (ref "DIR") (pin "4") (pinfunction "S_4") (pintype "passive"))
      (node (ref "R7") (pin "2") (pinfunction "2_2") (pintype "passive"))
      (node (ref "R8") (pin "1") (pinfunction "1_1") (pintype "passive"))
    )
    (net (code "22") (name "Net-(DREHZAHL-Pad1)") (class "Default")
      (node (ref "DREHZAHL") (pin "1") (pinfunction "1_1") (pintype "passive"))
      (node (ref "R14") (pin "2") (pinfunction "2_2") (pintype "passive"))
      (node (ref "R15") (pin "2") (pinfunction "2_2") (pintype "passive"))
    )
    (net (code "23") (name "Net-(ENCB-S)") (class "Default")
      (node (ref "ENC") (pin "2") (pinfunction "S_2") (pintype "passive"))
      (node (ref "R25") (pin "2") (pinfunction "2_2") (pintype "passive"))
      (node (ref "R27") (pin "2") (pinfunction "2_2") (pintype "passive"))
    )
    (net (code "24") (name "Net-(ENCC-S)") (class "Default")
      (node (ref "ENC") (pin "3") (pinfunction "S_3") (pintype "passive"))
      (node (ref "R26") (pin "2") (pinfunction "2_2") (pintype "passive"))
      (node (ref "R28") (pin "2") (pinfunction "2_2") (pintype "passive"))
    )
    (net (code "25") (name "Net-(J1-1-PadA1)") (class "Default")
      (node (ref "J1") (pin "A1") (pinfunction "1_A1") (pintype "passive"))
      (node (ref "J1") (pin "A2") (pinfunction "1_A2") (pintype "passive"))
      (node (ref "SV1") (pin "AC/L") (pinfunction "AC/L_AC/L") (pintype "bidirectional"))
    )
    (net (code "26") (name "Net-(M1-ADC6)") (class "Default")
      (node (ref "C2") (pin "1") (pinfunction "1_1") (pintype "passive"))
      (node (ref "M1") (pin "J3.2") (pinfunction "ADC6_J3.2") (pintype "bidirectional"))
      (node (ref "R11") (pin "1") (pinfunction "1_1") (pintype "passive"))
    )
    (net (code "27") (name "Net-(M1-PC2)") (class "Default")
      (node (ref "C16") (pin "1") (pinfunction "1_1") (pintype "passive"))
      (node (ref "M1") (pin "J6.6") (pinfunction "PC2_J6.6") (pintype "bidirectional"))
      (node (ref "R26") (pin "1") (pinfunction "1_1") (pintype "passive"))
    )
    (net (code "28") (name "Net-(M1-PC3)") (class "Default")
      (node (ref "C11") (pin "1") (pinfunction "1_1") (pintype "passive"))
      (node (ref "M1") (pin "J6.5") (pinfunction "PC3_J6.5") (pintype "bidirectional"))
      (node (ref "R25") (pin "1") (pinfunction "1_1") (pintype "passive"))
    )
    (net (code "29") (name "Net-(OK2-A)") (class "Default")
      (node (ref "OK2") (pin "1") (pinfunction "A_1") (pintype "passive"))
      (node (ref "R1") (pin "2") (pinfunction "2_2") (pintype "passive"))
    )
    (net (code "30") (name "Net-(R1-Pad1)") (class "Default")
      (node (ref "R1") (pin "1") (pinfunction "1_1") (pintype "passive"))
      (node (ref "T2") (pin "C") (pinfunction "C_C") (pintype "passive"))
    )
    (net (code "31") (name "Net-(R2-Pad1)") (class "Default")
      (node (ref "R2") (pin "1") (pinfunction "1_1") (pintype "passive"))
      (node (ref "T3") (pin "B") (pinfunction "B_B") (pintype "passive"))
    )
    (net (code "32") (name "Net-(R3-Pad1)") (class "Default")
      (node (ref "R3") (pin "1") (pinfunction "1_1") (pintype "passive"))
      (node (ref "T4") (pin "B") (pinfunction "B_B") (pintype "passive"))
    )
    (net (code "33") (name "Net-(R4-Pad1)") (class "Default")
      (node (ref "R4") (pin "1") (pinfunction "1_1") (pintype "passive"))
      (node (ref "T2") (pin "B") (pinfunction "B_B") (pintype "passive"))
    )
    (net (code "34") (name "Net-(R5-Pad1)") (class "Default")
      (node (ref "R5") (pin "1") (pinfunction "1_1") (pintype "passive"))
      (node (ref "T1") (pin "B") (pinfunction "B_B") (pintype "passive"))
    )
    (net (code "35") (name "Net-(R6-Pad2)") (class "Default")
      (node (ref "R6") (pin "2") (pinfunction "2_2") (pintype "passive"))
      (node (ref "T1") (pin "C") (pinfunction "C_C") (pintype "passive"))
    )
    (net (code "36") (name "Net-(R11-Pad2)") (class "Default")
      (node (ref "R11") (pin "2") (pinfunction "2_2") (pintype "passive"))
      (node (ref "R12") (pin "1") (pinfunction "1_1") (pintype "passive"))
      (node (ref "R13") (pin "2") (pinfunction "2_2") (pintype "passive"))
    )
    (net (code "37") (name "Net-(R16-Pad2)") (class "Default")
      (node (ref "R16") (pin "2") (pinfunction "2_2") (pintype "passive"))
      (node (ref "R17") (pin "2") (pinfunction "2_2") (pintype "passive"))
      (node (ref "SECURSW") (pin "1") (pinfunction "1_1") (pintype "passive"))
    )
    (net (code "38") (name "Net-(R22-Pad1)") (class "Default")
      (node (ref "R22") (pin "1") (pinfunction "1_1") (pintype "passive"))
      (node (ref "T5") (pin "B") (pinfunction "B_B") (pintype "passive"))
    )
    (net (code "39") (name "Net-(R31-Pad2)") (class "Default")
      (node (ref "R31") (pin "2") (pinfunction "2_2") (pintype "passive"))
      (node (ref "T4") (pin "C") (pinfunction "C_C") (pintype "passive"))
    )
    (net (code "40") (name "Net-(STARTB-S)") (class "Default")
      (node (ref "R30") (pin "1") (pinfunction "1_1") (pintype "passive"))
      (node (ref "START") (pin "2") (pinfunction "S_2") (pintype "passive"))
    )
    (net (code "41") (name "Net-(STOPB-S)") (class "Default")
      (node (ref "R31") (pin "1") (pinfunction "1_1") (pintype "passive"))
      (node (ref "STOP") (pin "2") (pinfunction "S_2") (pintype "passive"))
    )
    (net (code "42") (name "Net-(U1A-QC)") (class "Default")
      (node (ref "R21") (pin "1") (pinfunction "1_1") (pintype "passive"))
      (node (ref "U1") (pin "5") (pinfunction "QC_5") (pintype "output"))
    )
    (net (code "43") (name "Net-(U1A-QH)") (class "Default")
      (node (ref "U1") (pin "13") (pinfunction "QH_13") (pintype "output"))
      (node (ref "U2") (pin "1") (pinfunction "A_1") (pintype "input"))
      (node (ref "U2") (pin "2") (pinfunction "B_2") (pintype "input"))
    )
    (net (code "44") (name "Net-(U2A-QE)") (class "Default")
      (node (ref "R22") (pin "2") (pinfunction "2_2") (pintype "passive"))
      (node (ref "U2") (pin "10") (pinfunction "QE_10") (pintype "output"))
    )
    (net (code "45") (name "Net-(U3A-QH)") (class "Default")
      (node (ref "U3") (pin "9") (pinfunction "QH_9") (pintype "output"))
      (node (ref "U4") (pin "5") (pinfunction "I1_5") (pintype "input"))
    )
    (net (code "46") (name "Net-(U4A-I0)") (class "Default")
      (node (ref "U4") (pin "1") (pinfunction "I0_1") (pintype "input"))
      (node (ref "U4") (pin "8") (pinfunction "O_8") (pintype "output"))
    )
    (net (code "47") (name "Net-(U4A-I1)") (class "Default")
      (node (ref "U4") (pin "2") (pinfunction "I1_2") (pintype "input"))
      (node (ref "U4") (pin "6") (pinfunction "O_6") (pintype "output"))
    )
    (net (code "48") (name "Net-(U4B-I0)") (class "Default")
      (node (ref "U4") (pin "11") (pinfunction "O_11") (pintype "output"))
      (node (ref "U4") (pin "4") (pinfunction "I0_4") (pintype "input"))
    )
    (net (code "49") (name "Net-(U5A-I)") (class "Default")
      (node (ref "C3") (pin "2") (pinfunction "2_2") (pintype "passive"))
      (node (ref "R15") (pin "1") (pinfunction "1_1") (pintype "passive"))
      (node (ref "U5") (pin "2") (pinfunction "I_2") (pintype "input"))
    )
    (net (code "50") (name "Net-(U6-AO)") (class "Default")
      (node (ref "R18") (pin "2") (pinfunction "2_2") (pintype "passive"))
      (node (ref "SJ2") (pin "1") (pinfunction "1_1") (pintype "passive"))
      (node (ref "U6") (pin "6") (pinfunction "AO_6") (pintype "bidirectional"))
    )
    (net (code "51") (name "Net-(U6-SCL)") (class "Default")
      (node (ref "R20") (pin "1") (pinfunction "1_1") (pintype "passive"))
      (node (ref "U6") (pin "5") (pinfunction "SCL_5") (pintype "bidirectional"))
      (node (ref "U7") (pin "3") (pinfunction "SCL1_3") (pintype "input"))
    )
    (net (code "52") (name "Net-(U6-SDA)") (class "Default")
      (node (ref "R19") (pin "1") (pinfunction "1_1") (pintype "passive"))
      (node (ref "U6") (pin "4") (pinfunction "SDA_4") (pintype "bidirectional"))
      (node (ref "U7") (pin "2") (pinfunction "SDA1_2") (pintype "input"))
    )
    (net (code "53") (name "ONEWIRE") (class "Default")
      (node (ref "M1") (pin "J6.8") (pinfunction "PC0_J6.8") (pintype "bidirectional"))
      (node (ref "R24") (pin "1") (pinfunction "1_1") (pintype "passive"))
      (node (ref "TEMP") (pin "2") (pinfunction "S_2") (pintype "passive"))
    )
    (net (code "54") (name "RPM_SENSOR") (class "Default")
      (node (ref "M1") (pin "J7.2") (pinfunction "PB0_J7.2") (pintype "bidirectional"))
      (node (ref "U5") (pin "4") (pinfunction "O_4") (pintype "output"))
    )
    (net (code "55") (name "RST") (class "Default")
      (node (ref "ISP") (pin "1") (pinfunction "S_1") (pintype "passive"))
      (node (ref "M1") (pin "J6.3") (pinfunction "RST.1_J6.3") (pintype "bidirectional"))
      (node (ref "M1") (pin "J7.10") (pinfunction "RST.2_J7.10") (pintype "bidirectional"))
    )
    (net (code "56") (name "SCK") (class "Default")
      (node (ref "ISP") (pin "2") (pinfunction "S_2") (pintype "passive"))
      (node (ref "M1") (pin "J6.9") (pinfunction "SCK/PB5_J6.9") (pintype "bidirectional"))
    )
    (net (code "57") (name "SCL") (class "Default")
      (node (ref "DISPLAY") (pin "3") (pinfunction "S_3") (pintype "passive"))
      (node (ref "M1") (pin "J2.2") (pinfunction "SCL/PC5_J2.2") (pintype "bidirectional"))
      (node (ref "R9") (pin "2") (pinfunction "2_2") (pintype "passive"))
      (node (ref "U7") (pin "6") (pinfunction "SCL2_6") (pintype "output"))
    )
    (net (code "58") (name "SDA") (class "Default")
      (node (ref "DISPLAY") (pin "4") (pinfunction "S_4") (pintype "passive"))
      (node (ref "M1") (pin "J2.1") (pinfunction "SDA/PC4_J2.1") (pintype "bidirectional"))
      (node (ref "R10") (pin "2") (pinfunction "2_2") (pintype "passive"))
      (node (ref "U7") (pin "7") (pinfunction "SDA2_7") (pintype "output"))
    )
    (net (code "59") (name "SECURITY_SW") (class "Default")
      (node (ref "C4") (pin "1") (pinfunction "1_1") (pintype "passive"))
      (node (ref "M1") (pin "J7.8") (pinfunction "PD2/INT0_J7.8") (pintype "bidirectional"))
      (node (ref "R17") (pin "1") (pinfunction "1_1") (pintype "passive"))
    )
    (net (code "60") (name "SH{slash}LD_SWITCH") (class "Default")
      (node (ref "J3") (pin "6") (pinfunction "S_6") (pintype "passive"))
      (node (ref "J4") (pin "2") (pinfunction "S_2") (pintype "passive"))
      (node (ref "U3") (pin "1") (pinfunction "SH/~{LD}_1") (pintype "input"))
    )
    (net (code "61") (name "SMC_LED") (class "Default")
      (node (ref "M1") (pin "J7.3") (pinfunction "PD7_J7.3") (pintype "bidirectional"))
      (node (ref "OK1") (pin "4") (pinfunction "COL_4") (pintype "passive"))
    )
    (net (code "62") (name "SMC_SW") (class "Default")
      (node (ref "M1") (pin "J7.4") (pinfunction "PD6/OC0A_J7.4") (pintype "bidirectional"))
      (node (ref "R4") (pin "2") (pinfunction "2_2") (pintype "passive"))
    )
    (net (code "63") (name "STARTLED") (class "Default")
      (node (ref "R30") (pin "2") (pinfunction "2_2") (pintype "passive"))
      (node (ref "T3") (pin "C") (pinfunction "C_C") (pintype "passive"))
    )
    (net (code "64") (name "START_LED_") (class "Default")
      (node (ref "ISP") (pin "4") (pinfunction "S_4") (pintype "passive"))
      (node (ref "M1") (pin "J6.11") (pinfunction "MOSI/PB3_J6.11") (pintype "bidirectional"))
      (node (ref "R2") (pin "2") (pinfunction "2_2") (pintype "passive"))
    )
    (net (code "65") (name "START_SW") (class "Default")
      (node (ref "M1") (pin "J7.6") (pinfunction "PD4_J7.6") (pintype "bidirectional"))
      (node (ref "START") (pin "4") (pinfunction "S_4") (pintype "passive"))
    )
    (net (code "66") (name "STOP_LED_") (class "Default")
      (node (ref "M1") (pin "J6.12") (pinfunction "OC1B/PB2_J6.12") (pintype "bidirectional"))
      (node (ref "R3") (pin "2") (pinfunction "2_2") (pintype "passive"))
    )
    (net (code "67") (name "STOP_SW") (class "Default")
      (node (ref "M1") (pin "J7.7") (pinfunction "PD3/INT1_J7.7") (pintype "bidirectional"))
      (node (ref "STOP") (pin "4") (pinfunction "S_4") (pintype "passive"))
    )
    (net (code "68") (name "VOUT") (class "Default")
      (node (ref "J9") (pin "2") (pinfunction "S_2") (pintype "passive"))
      (node (ref "J9A-") (pin "2") (pinfunction "1_2") (pintype "passive"))
      (node (ref "U6") (pin "1") (pinfunction "VOUT_1") (pintype "bidirectional"))
    )
    (net (code "69") (name "unconnected-(F2-Pad1B)") (class "Default")
      (node (ref "F2") (pin "1B") (pinfunction "1B_1B") (pintype "passive"))
    )
    (net (code "70") (name "unconnected-(F2-Pad2B)") (class "Default")
      (node (ref "F2") (pin "2B") (pinfunction "2B_2B") (pintype "passive"))
    )
    (net (code "71") (name "unconnected-(M1-ADC7-PadJ3.3)") (class "Default")
      (node (ref "M1") (pin "J3.3") (pinfunction "ADC7_J3.3") (pintype "bidirectional"))
    )
    (net (code "72") (name "unconnected-(M1-PD0{slash}RX-PadJ7.11)") (class "Default")
      (node (ref "M1") (pin "J7.11") (pinfunction "PD0/RX_J7.11") (pintype "bidirectional"))
    )
    (net (code "73") (name "unconnected-(M1-PD1{slash}TX-PadJ7.12)") (class "Default")
      (node (ref "M1") (pin "J7.12") (pinfunction "PD1/TX_J7.12") (pintype "bidirectional"))
    )
    (net (code "74") (name "unconnected-(M1-P_CTS-PadJ1.5)") (class "Default")
      (node (ref "M1") (pin "J1.5") (pinfunction "P_CTS_J1.5") (pintype "bidirectional"))
    )
    (net (code "75") (name "unconnected-(M1-P_DTR-PadJ1.1)") (class "Default")
      (node (ref "M1") (pin "J1.1") (pinfunction "P_DTR_J1.1") (pintype "bidirectional"))
    )
    (net (code "76") (name "unconnected-(M1-P_RXD-PadJ1.2)") (class "Default")
      (node (ref "M1") (pin "J1.2") (pinfunction "P_RXD_J1.2") (pintype "bidirectional"))
    )
    (net (code "77") (name "unconnected-(M1-P_TXD-PadJ1.3)") (class "Default")
      (node (ref "M1") (pin "J1.3") (pinfunction "P_TXD_J1.3") (pintype "bidirectional"))
    )
    (net (code "78") (name "unconnected-(U1A-QA-Pad3)") (class "Default")
      (node (ref "U1") (pin "3") (pinfunction "QA_3") (pintype "output"))
    )
    (net (code "79") (name "unconnected-(U1A-QB-Pad4)") (class "Default")
      (node (ref "U1") (pin "4") (pinfunction "QB_4") (pintype "output"))
    )
    (net (code "80") (name "unconnected-(U1A-QD-Pad6)") (class "Default")
      (node (ref "U1") (pin "6") (pinfunction "QD_6") (pintype "output"))
    )
    (net (code "81") (name "unconnected-(U1A-QE-Pad10)") (class "Default")
      (node (ref "U1") (pin "10") (pinfunction "QE_10") (pintype "output"))
    )
    (net (code "82") (name "unconnected-(U1A-QF-Pad11)") (class "Default")
      (node (ref "U1") (pin "11") (pinfunction "QF_11") (pintype "output"))
    )
    (net (code "83") (name "unconnected-(U1A-QG-Pad12)") (class "Default")
      (node (ref "U1") (pin "12") (pinfunction "QG_12") (pintype "output"))
    )
    (net (code "84") (name "unconnected-(U2A-QA-Pad3)") (class "Default")
      (node (ref "U2") (pin "3") (pinfunction "QA_3") (pintype "output"))
    )
    (net (code "85") (name "unconnected-(U2A-QB-Pad4)") (class "Default")
      (node (ref "U2") (pin "4") (pinfunction "QB_4") (pintype "output"))
    )
    (net (code "86") (name "unconnected-(U2A-QC-Pad5)") (class "Default")
      (node (ref "U2") (pin "5") (pinfunction "QC_5") (pintype "output"))
    )
    (net (code "87") (name "unconnected-(U2A-QD-Pad6)") (class "Default")
      (node (ref "U2") (pin "6") (pinfunction "QD_6") (pintype "output"))
    )
    (net (code "88") (name "unconnected-(U2A-QF-Pad11)") (class "Default")
      (node (ref "U2") (pin "11") (pinfunction "QF_11") (pintype "output"))
    )
    (net (code "89") (name "unconnected-(U2A-QG-Pad12)") (class "Default")
      (node (ref "U2") (pin "12") (pinfunction "QG_12") (pintype "output"))
    )
    (net (code "90") (name "unconnected-(U2A-QH-Pad13)") (class "Default")
      (node (ref "U2") (pin "13") (pinfunction "QH_13") (pintype "output"))
    )
    (net (code "91") (name "unconnected-(U3A-~{QH}-Pad7)") (class "Default")
      (node (ref "U3") (pin "7") (pinfunction "~{QH}_7") (pintype "output"))
    )
  )
)
